# CloseLoopStepperMotor.net
KiCad netlist of a schematic drawn in Altium Designer
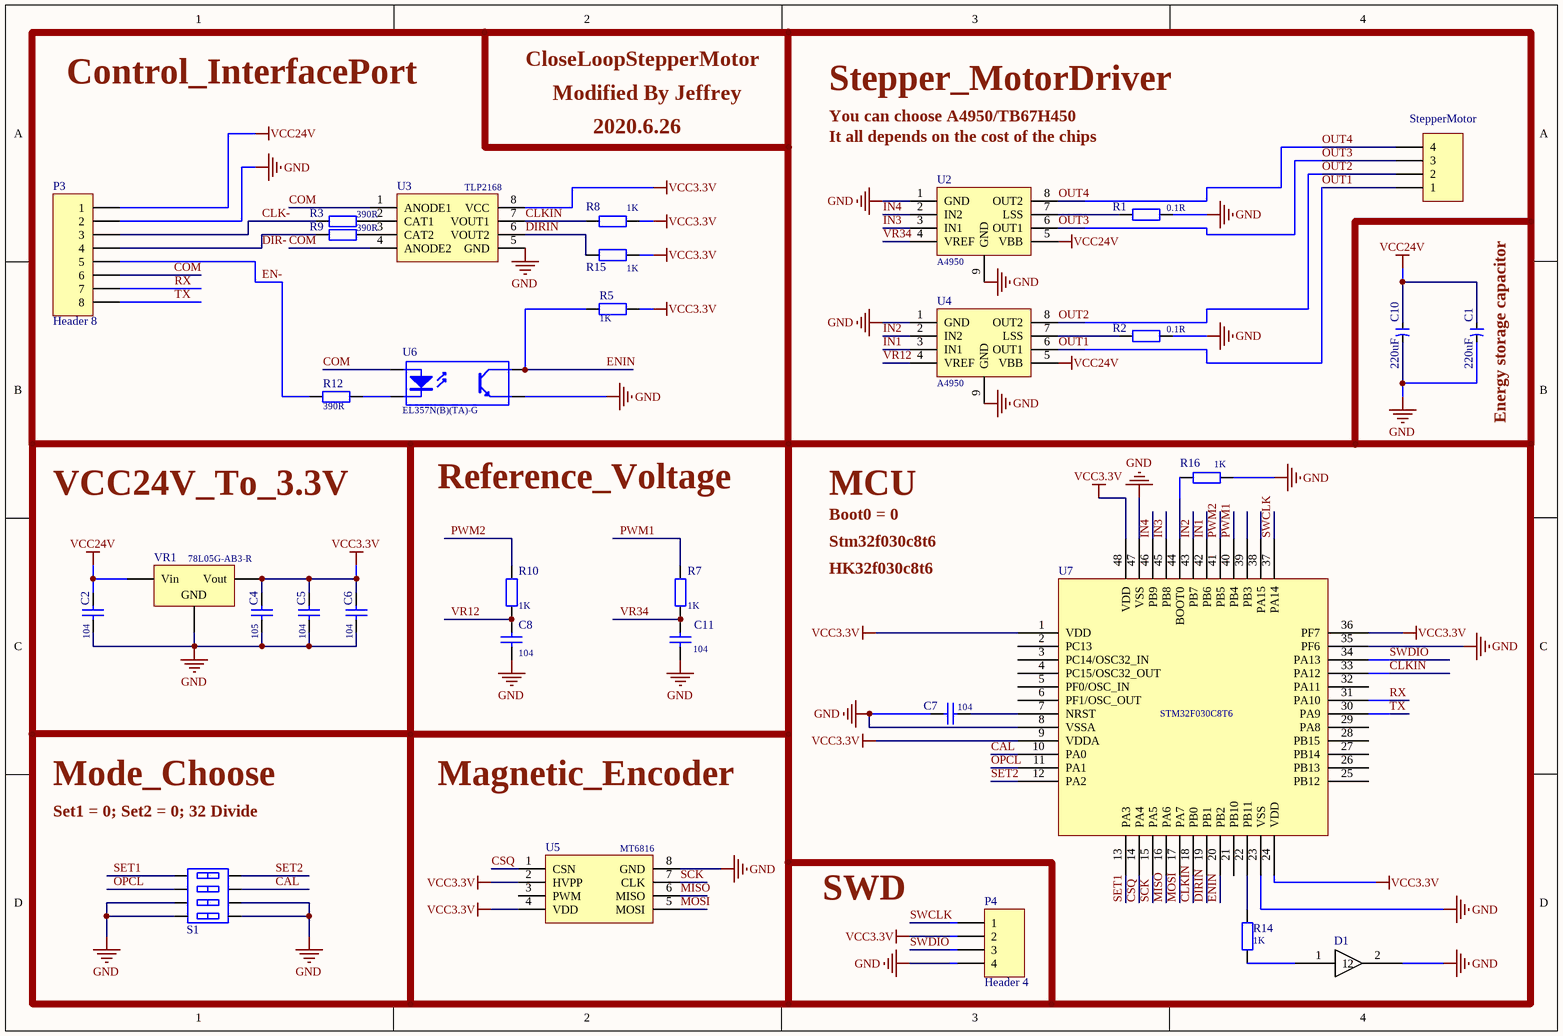
[diagram p0: CloseLoopStepperMotor.SchDoc]

(export (version "E")
  (design (tool "Eeschema 10.0.6"))
  (components
    (comp (ref "C1")
      (value "220uF")
      (footprint "CAP 2.5*6.3*11.2 - GD")
      (description "Polarized Capacitor (Axial)")
      (fields (field (name "Comment") "CAP POL") (field (name "PUBLISHER") "Altium Limited"))
      (libsource (lib "MySchib") (part "CAP POL"))
    )
    (comp (ref "C2")
      (value "104")
      (footprint "C 0603_M")
      (description "贴片电容")
      (libsource (lib "Miscellaneous Devices LC") (part "0805 100nF(104) 10% 50V"))
    )
    (comp (ref "C4")
      (value "105")
      (footprint "C 0603_M")
      (description "贴片电容")
      (libsource (lib "Miscellaneous Devices LC") (part "0805 1uF (105) 10% 50V"))
    )
    (comp (ref "C5")
      (value "104")
      (footprint "C 0603_M")
      (description "贴片电容")
      (libsource (lib "Miscellaneous Devices LC") (part "0805 100nF(104) 10% 50V"))
    )
    (comp (ref "C6")
      (value "104")
      (footprint "C 0603_M")
      (description "贴片电容")
      (libsource (lib "Miscellaneous Devices LC") (part "0805 100nF(104) 10% 50V"))
    )
    (comp (ref "C7")
      (value "104")
      (footprint "C 0603_M")
      (description "贴片电容")
      (libsource (lib "Miscellaneous Devices LC") (part "0805 100nF(104) 10% 50V"))
    )
    (comp (ref "C8")
      (value "104")
      (footprint "C 0603_M")
      (description "贴片电容")
      (libsource (lib "Miscellaneous Devices LC") (part "0805 100nF(104) 10% 50V"))
    )
    (comp (ref "C10")
      (value "220uF")
      (footprint "CAP 2.5*6.3*11.2 - GD")
      (description "Polarized Capacitor (Axial)")
      (fields (field (name "Comment") "CAP POL") (field (name "PUBLISHER") "Altium Limited"))
      (libsource (lib "MySchib") (part "CAP POL"))
    )
    (comp (ref "C11")
      (value "104")
      (footprint "C 0603_M")
      (description "贴片电容")
      (libsource (lib "Miscellaneous Devices LC") (part "0805 100nF(104) 10% 50V"))
    )
    (comp (ref "D1")
      (value "~")
      (footprint "LED 0603B")
      (libsource (lib "CloseLoopStepperMotor") (part "Diode"))
    )
    (comp (ref "P3")
      (value "Header 8")
      (footprint "PH2.0-WS-8P")
      (description "Header, 8-Pin")
      (fields (field (name "PUBLISHER") "Altium Limited"))
      (libsource (lib "Miscellaneous Connectors") (part "Header 8"))
    )
    (comp (ref "P4")
      (value "Header 4")
      (footprint "HDR2.54-LI-4P")
      (description "Header, 4-Pin")
      (fields (field (name "PUBLISHER") "Altium Limited"))
      (libsource (lib "Miscellaneous Connectors") (part "Header 4"))
    )
    (comp (ref "R1")
      (value "0.1R")
      (footprint "1206_R")
      (description "贴片电阻")
      (libsource (lib "Miscellaneous Devices LC") (part "1206 0.1Ω (R100) 1%"))
    )
    (comp (ref "R2")
      (value "0.1R")
      (footprint "1206_R")
      (description "贴片电阻")
      (libsource (lib "Miscellaneous Devices LC") (part "1206 0.1Ω (R100) 1%"))
    )
    (comp (ref "R3")
      (value "390R")
      (footprint "R 0603_M")
      (description "贴片电阻")
      (libsource (lib "Miscellaneous Devices LC") (part "0805 390Ω (3900) 1%"))
    )
    (comp (ref "R5")
      (value "1K")
      (footprint "R 0603_M")
      (description "贴片电阻")
      (libsource (lib "") (part "0805 1KΩ (1001) 1%_2"))
    )
    (comp (ref "R7")
      (value "1K")
      (footprint "R 0603_M")
      (description "贴片电阻")
      (libsource (lib "Miscellaneous Devices LC") (part "0805 1KΩ (1001) 1%"))
    )
    (comp (ref "R8")
      (value "1K")
      (footprint "R 0603_M")
      (description "贴片电阻")
      (libsource (lib "") (part "0805 1KΩ (1001) 1%_2"))
    )
    (comp (ref "R9")
      (value "390R")
      (footprint "R 0603_M")
      (description "贴片电阻")
      (libsource (lib "Miscellaneous Devices LC") (part "0805 390Ω (3900) 1%"))
    )
    (comp (ref "R10")
      (value "1K")
      (footprint "R 0603_M")
      (description "贴片电阻")
      (libsource (lib "") (part "0805 1KΩ (1001) 1%_1"))
    )
    (comp (ref "R12")
      (value "390R")
      (footprint "R 0603_M")
      (description "贴片电阻")
      (libsource (lib "Miscellaneous Devices LC") (part "0805 390Ω (3900) 1%"))
    )
    (comp (ref "R14")
      (value "1K")
      (footprint "R 0603_M")
      (description "贴片电阻")
      (libsource (lib "") (part "0805 1KΩ (1001) 1%_1"))
    )
    (comp (ref "R15")
      (value "1K")
      (footprint "R 0603_M")
      (description "贴片电阻")
      (libsource (lib "") (part "0805 1KΩ (1001) 1%_3"))
    )
    (comp (ref "R16")
      (value "1K")
      (footprint "R 0603_M")
      (description "贴片电阻")
      (libsource (lib "") (part "0805 1KΩ (1001) 1%_2"))
    )
    (comp (ref "S1")
      (value "SWDIP-4")
      (footprint "CSW1.27 SMD-4P")
      (description "DIP Switch, 4Position, SPST")
      (fields (field (name "PUBLISHER") "Altium Limited"))
      (libsource (lib "MySchib") (part "SWDIP-4"))
    )
    (comp (ref "StepperMotor")
      (value "HEADER4")
      (footprint "XH2.54-LI-4P")
      (description "Header, 4-Pin")
      (fields (field (name "PUBLISHER") "Altium Limited"))
      (libsource (lib "MySchib") (part "HEADER4"))
    )
    (comp (ref "U2")
      (value "A4950")
      (footprint "SOP8_M")
      (description "Dual Full-Bridge  DMOS PWM Motor Driver")
      (libsource (lib "MySchib") (part "A4950"))
    )
    (comp (ref "U3")
      (value "TLP2168")
      (footprint "SOP8_M")
      (description "HIGH SPEED 10MBit/s LOGIC GATE  PHOTOCOUPLER")
      (libsource (lib "MySchib") (part "TLP2168"))
    )
    (comp (ref "U4")
      (value "A4950")
      (footprint "SOP8_M")
      (description "Dual Full-Bridge  DMOS PWM Motor Driver")
      (libsource (lib "MySchib") (part "A4950"))
    )
    (comp (ref "U5")
      (value "MT6816")
      (footprint "SOP8_M")
      (description "GMR-Based Angle Sensor")
      (libsource (lib "MySchib") (part "MT6816"))
    )
    (comp (ref "U6")
      (value "EL357N(B)(TA)-G")
      (footprint "SOP4_M")
      (description "贴片光耦")
      (libsource (lib "Miscellaneous Devices LC") (part "EL357N(B)(TA)-G_[C6649]"))
    )
    (comp (ref "U7")
      (value "STM32F030C8T6")
      (footprint "LQFP48 7X7_M")
      (description "ARM")
      (libsource (lib "Miscellaneous Devices LC") (part "STM32F030C8T6"))
    )
    (comp (ref "VR1")
      (value "78L05G-AB3-R")
      (footprint "SOT-89(SOT-89-3)")
      (description "低压差线性稳压(LDO)")
      (libsource (lib "Miscellaneous Devices LC") (part "SOT-89 78L05G-AB3-R"))
    )
  )
  (nets
    (net (code "1") (name "/CAL") (class "Default")
      (node (ref "S1") (pin "4") (pinfunction "B2_4") (pintype "passive"))
      (node (ref "U7") (pin "10") (pinfunction "PA0_10") (pintype "passive"))
    )
    (net (code "2") (name "/CLK-") (class "Default")
      (node (ref "P3") (pin "3") (pinfunction "3_3") (pintype "passive"))
      (node (ref "R3") (pin "1") (pinfunction "1_1") (pintype "passive"))
    )
    (net (code "3") (name "/CLKIN") (class "Default")
      (node (ref "R8") (pin "1") (pinfunction "1_1") (pintype "passive"))
      (node (ref "U3") (pin "7") (pinfunction "VOUT1_7") (pintype "passive"))
      (node (ref "U7") (pin "18") (pinfunction "PB0_18") (pintype "passive"))
      (node (ref "U7") (pin "33") (pinfunction "PA12_33") (pintype "passive"))
    )
    (net (code "4") (name "/COM") (class "Default")
      (node (ref "P3") (pin "6") (pinfunction "6_6") (pintype "passive"))
      (node (ref "U3") (pin "1") (pinfunction "ANODE1_1") (pintype "passive"))
      (node (ref "U3") (pin "4") (pinfunction "ANODE2_4") (pintype "passive"))
      (node (ref "U6") (pin "1") (pinfunction "A_1") (pintype "passive"))
    )
    (net (code "5") (name "/CSQ") (class "Default")
      (node (ref "U5") (pin "1") (pinfunction "CSN_1") (pintype "passive"))
      (node (ref "U7") (pin "14") (pinfunction "PA4_14") (pintype "passive"))
    )
    (net (code "6") (name "/DIR-") (class "Default")
      (node (ref "P3") (pin "4") (pinfunction "4_4") (pintype "passive"))
      (node (ref "R9") (pin "1") (pinfunction "1_1") (pintype "passive"))
    )
    (net (code "7") (name "/DIRIN") (class "Default")
      (node (ref "R15") (pin "2") (pinfunction "2_2") (pintype "passive"))
      (node (ref "U3") (pin "6") (pinfunction "VOUT2_6") (pintype "passive"))
      (node (ref "U7") (pin "19") (pinfunction "PB1_19") (pintype "passive"))
    )
    (net (code "8") (name "/EN-") (class "Default")
      (node (ref "P3") (pin "5") (pinfunction "5_5") (pintype "passive"))
      (node (ref "R12") (pin "1") (pinfunction "1_1") (pintype "passive"))
    )
    (net (code "9") (name "/ENIN") (class "Default")
      (node (ref "R5") (pin "1") (pinfunction "1_1") (pintype "passive"))
      (node (ref "U6") (pin "4") (pinfunction "C_4") (pintype "passive"))
      (node (ref "U7") (pin "20") (pinfunction "PB2_20") (pintype "passive"))
    )
    (net (code "10") (name "/IN1") (class "Default")
      (node (ref "U4") (pin "3") (pinfunction "IN1_3") (pintype "passive"))
      (node (ref "U7") (pin "42") (pinfunction "PB6_42") (pintype "passive"))
    )
    (net (code "11") (name "/IN2") (class "Default")
      (node (ref "U4") (pin "2") (pinfunction "IN2_2") (pintype "passive"))
      (node (ref "U7") (pin "43") (pinfunction "PB7_43") (pintype "passive"))
    )
    (net (code "12") (name "/IN3") (class "Default")
      (node (ref "U2") (pin "3") (pinfunction "IN1_3") (pintype "passive"))
      (node (ref "U7") (pin "45") (pinfunction "PB8_45") (pintype "passive"))
    )
    (net (code "13") (name "/IN4") (class "Default")
      (node (ref "U2") (pin "2") (pinfunction "IN2_2") (pintype "passive"))
      (node (ref "U7") (pin "46") (pinfunction "PB9_46") (pintype "passive"))
    )
    (net (code "14") (name "/MISO") (class "Default")
      (node (ref "U5") (pin "6") (pinfunction "MISO_6") (pintype "passive"))
      (node (ref "U7") (pin "16") (pinfunction "PA6_16") (pintype "passive"))
    )
    (net (code "15") (name "/MOSI") (class "Default")
      (node (ref "U5") (pin "5") (pinfunction "MOSI_5") (pintype "passive"))
      (node (ref "U7") (pin "17") (pinfunction "PA7_17") (pintype "passive"))
    )
    (net (code "16") (name "/OPCL") (class "Default")
      (node (ref "S1") (pin "3") (pinfunction "A2_3") (pintype "passive"))
      (node (ref "U7") (pin "11") (pinfunction "PA1_11") (pintype "passive"))
    )
    (net (code "17") (name "/OUT1") (class "Default")
      (node (ref "StepperMotor") (pin "1") (pinfunction "1_1") (pintype "passive"))
      (node (ref "U4") (pin "6") (pinfunction "OUT1_6") (pintype "passive"))
    )
    (net (code "18") (name "/OUT2") (class "Default")
      (node (ref "StepperMotor") (pin "2") (pinfunction "2_2") (pintype "passive"))
      (node (ref "U4") (pin "8") (pinfunction "OUT2_8") (pintype "passive"))
    )
    (net (code "19") (name "/OUT3") (class "Default")
      (node (ref "StepperMotor") (pin "3") (pinfunction "3_3") (pintype "passive"))
      (node (ref "U2") (pin "6") (pinfunction "OUT1_6") (pintype "passive"))
    )
    (net (code "20") (name "/OUT4") (class "Default")
      (node (ref "StepperMotor") (pin "4") (pinfunction "4_4") (pintype "passive"))
      (node (ref "U2") (pin "8") (pinfunction "OUT2_8") (pintype "passive"))
    )
    (net (code "21") (name "/PWM1") (class "Default")
      (node (ref "R7") (pin "2") (pinfunction "2_2") (pintype "passive"))
      (node (ref "U7") (pin "40") (pinfunction "PB4_40") (pintype "passive"))
    )
    (net (code "22") (name "/PWM2") (class "Default")
      (node (ref "R10") (pin "1") (pinfunction "1_1") (pintype "passive"))
      (node (ref "U7") (pin "41") (pinfunction "PB5_41") (pintype "passive"))
    )
    (net (code "23") (name "/RX") (class "Default")
      (node (ref "P3") (pin "7") (pinfunction "7_7") (pintype "passive"))
      (node (ref "U7") (pin "31") (pinfunction "PA10_31") (pintype "passive"))
    )
    (net (code "24") (name "/SCK") (class "Default")
      (node (ref "U5") (pin "7") (pinfunction "CLK_7") (pintype "passive"))
      (node (ref "U7") (pin "15") (pinfunction "PA5_15") (pintype "passive"))
    )
    (net (code "25") (name "/SET1") (class "Default")
      (node (ref "S1") (pin "1") (pinfunction "A1_1") (pintype "passive"))
      (node (ref "U7") (pin "13") (pinfunction "PA3_13") (pintype "passive"))
    )
    (net (code "26") (name "/SET2") (class "Default")
      (node (ref "S1") (pin "2") (pinfunction "B1_2") (pintype "passive"))
      (node (ref "U7") (pin "12") (pinfunction "PA2_12") (pintype "passive"))
    )
    (net (code "27") (name "/SWCLK") (class "Default")
      (node (ref "P4") (pin "1") (pinfunction "1_1") (pintype "passive"))
      (node (ref "U7") (pin "37") (pinfunction "PA14_37") (pintype "passive"))
    )
    (net (code "28") (name "/SWDIO") (class "Default")
      (node (ref "P4") (pin "3") (pinfunction "3_3") (pintype "passive"))
      (node (ref "U7") (pin "34") (pinfunction "PA13_34") (pintype "passive"))
    )
    (net (code "29") (name "/TX") (class "Default")
      (node (ref "P3") (pin "8") (pinfunction "8_8") (pintype "passive"))
      (node (ref "U7") (pin "30") (pinfunction "PA9_30") (pintype "passive"))
    )
    (net (code "30") (name "/VR12") (class "Default")
      (node (ref "C8") (pin "1") (pinfunction "1_1") (pintype "passive"))
      (node (ref "R10") (pin "2") (pinfunction "2_2") (pintype "passive"))
      (node (ref "U4") (pin "4") (pinfunction "VREF_4") (pintype "passive"))
    )
    (net (code "31") (name "/VR34") (class "Default")
      (node (ref "C11") (pin "1") (pinfunction "1_1") (pintype "passive"))
      (node (ref "R7") (pin "1") (pinfunction "1_1") (pintype "passive"))
      (node (ref "U2") (pin "4") (pinfunction "VREF_4") (pintype "passive"))
    )
    (net (code "32") (name "GND") (class "Default")
      (node (ref "C1") (pin "2") (pinfunction "2_2") (pintype "passive"))
      (node (ref "C10") (pin "2") (pinfunction "2_2") (pintype "passive"))
      (node (ref "C11") (pin "2") (pinfunction "2_2") (pintype "passive"))
      (node (ref "C2") (pin "2") (pinfunction "2_2") (pintype "passive"))
      (node (ref "C4") (pin "2") (pinfunction "2_2") (pintype "passive"))
      (node (ref "C5") (pin "2") (pinfunction "2_2") (pintype "passive"))
      (node (ref "C6") (pin "2") (pinfunction "2_2") (pintype "passive"))
      (node (ref "C7") (pin "1") (pinfunction "1_1") (pintype "passive"))
      (node (ref "C8") (pin "2") (pinfunction "2_2") (pintype "passive"))
      (node (ref "D1") (pin "2") (pinfunction "2_2") (pintype "passive"))
      (node (ref "P3") (pin "2") (pinfunction "2_2") (pintype "passive"))
      (node (ref "P4") (pin "4") (pinfunction "4_4") (pintype "passive"))
      (node (ref "R1") (pin "1") (pinfunction "1_1") (pintype "passive"))
      (node (ref "R16") (pin "2") (pinfunction "2_2") (pintype "passive"))
      (node (ref "R2") (pin "1") (pinfunction "1_1") (pintype "passive"))
      (node (ref "S1") (pin "5") (pinfunction "A3_5") (pintype "passive"))
      (node (ref "S1") (pin "6") (pinfunction "B3_6") (pintype "passive"))
      (node (ref "S1") (pin "7") (pinfunction "A4_7") (pintype "passive"))
      (node (ref "S1") (pin "8") (pinfunction "B4_8") (pintype "passive"))
      (node (ref "U2") (pin "1") (pinfunction "GND_1") (pintype "passive"))
      (node (ref "U2") (pin "9") (pinfunction "GND_9") (pintype "passive"))
      (node (ref "U3") (pin "5") (pinfunction "GND_5") (pintype "passive"))
      (node (ref "U4") (pin "1") (pinfunction "GND_1") (pintype "passive"))
      (node (ref "U4") (pin "9") (pinfunction "GND_9") (pintype "passive"))
      (node (ref "U5") (pin "8") (pinfunction "GND_8") (pintype "passive"))
      (node (ref "U6") (pin "3") (pinfunction "E_3") (pintype "passive"))
      (node (ref "U7") (pin "23") (pinfunction "VSS_23") (pintype "passive"))
      (node (ref "U7") (pin "35") (pinfunction "PF6_35") (pintype "passive"))
      (node (ref "U7") (pin "47") (pinfunction "VSS_47") (pintype "passive"))
      (node (ref "U7") (pin "8") (pinfunction "VSSA_8") (pintype "passive"))
      (node (ref "VR1") (pin "2") (pinfunction "GND_2") (pintype "passive"))
    )
    (net (code "33") (name "Net-(D1-Pad1)") (class "Default")
      (node (ref "D1") (pin "1") (pinfunction "1_1") (pintype "passive"))
      (node (ref "R14") (pin "2") (pinfunction "2_2") (pintype "passive"))
    )
    (net (code "34") (name "Net-(U2-LSS)") (class "Default")
      (node (ref "R1") (pin "2") (pinfunction "2_2") (pintype "passive"))
      (node (ref "U2") (pin "7") (pinfunction "LSS_7") (pintype "passive"))
    )
    (net (code "35") (name "Net-(U3-CAT1)") (class "Default")
      (node (ref "R3") (pin "2") (pinfunction "2_2") (pintype "passive"))
      (node (ref "U3") (pin "2") (pinfunction "CAT1_2") (pintype "passive"))
    )
    (net (code "36") (name "Net-(U3-CAT2)") (class "Default")
      (node (ref "R9") (pin "2") (pinfunction "2_2") (pintype "passive"))
      (node (ref "U3") (pin "3") (pinfunction "CAT2_3") (pintype "passive"))
    )
    (net (code "37") (name "Net-(U4-LSS)") (class "Default")
      (node (ref "R2") (pin "2") (pinfunction "2_2") (pintype "passive"))
      (node (ref "U4") (pin "7") (pinfunction "LSS_7") (pintype "passive"))
    )
    (net (code "38") (name "Net-(U6-K)") (class "Default")
      (node (ref "R12") (pin "2") (pinfunction "2_2") (pintype "passive"))
      (node (ref "U6") (pin "2") (pinfunction "K_2") (pintype "passive"))
    )
    (net (code "39") (name "Net-(U7-BOOT0)") (class "Default")
      (node (ref "R16") (pin "1") (pinfunction "1_1") (pintype "passive"))
      (node (ref "U7") (pin "44") (pinfunction "BOOT0_44") (pintype "passive"))
    )
    (net (code "40") (name "Net-(U7-NRST)") (class "Default")
      (node (ref "C7") (pin "2") (pinfunction "2_2") (pintype "passive"))
      (node (ref "U7") (pin "7") (pinfunction "NRST_7") (pintype "passive"))
    )
    (net (code "41") (name "Net-(U7-PB11)") (class "Default")
      (node (ref "R14") (pin "1") (pinfunction "1_1") (pintype "passive"))
      (node (ref "U7") (pin "22") (pinfunction "PB11_22") (pintype "passive"))
    )
    (net (code "42") (name "VCC3.3V") (class "Default")
      (node (ref "C4") (pin "1") (pinfunction "1_1") (pintype "passive"))
      (node (ref "C5") (pin "1") (pinfunction "1_1") (pintype "passive"))
      (node (ref "C6") (pin "1") (pinfunction "1_1") (pintype "passive"))
      (node (ref "P4") (pin "2") (pinfunction "2_2") (pintype "passive"))
      (node (ref "R15") (pin "1") (pinfunction "1_1") (pintype "passive"))
      (node (ref "R5") (pin "2") (pinfunction "2_2") (pintype "passive"))
      (node (ref "R8") (pin "2") (pinfunction "2_2") (pintype "passive"))
      (node (ref "U3") (pin "8") (pinfunction "VCC_8") (pintype "passive"))
      (node (ref "U5") (pin "2") (pinfunction "HVPP_2") (pintype "passive"))
      (node (ref "U5") (pin "4") (pinfunction "VDD_4") (pintype "passive"))
      (node (ref "U7") (pin "1") (pinfunction "VDD_1") (pintype "passive"))
      (node (ref "U7") (pin "24") (pinfunction "VDD_24") (pintype "passive"))
      (node (ref "U7") (pin "36") (pinfunction "PF7_36") (pintype "passive"))
      (node (ref "U7") (pin "48") (pinfunction "VDD_48") (pintype "passive"))
      (node (ref "U7") (pin "9") (pinfunction "VDDA_9") (pintype "passive"))
      (node (ref "VR1") (pin "1") (pinfunction "Vout_1") (pintype "passive"))
    )
    (net (code "43") (name "VCC24V") (class "Default")
      (node (ref "C1") (pin "1") (pinfunction "1_1") (pintype "passive"))
      (node (ref "C10") (pin "1") (pinfunction "1_1") (pintype "passive"))
      (node (ref "C2") (pin "1") (pinfunction "1_1") (pintype "passive"))
      (node (ref "P3") (pin "1") (pinfunction "1_1") (pintype "passive"))
      (node (ref "U2") (pin "5") (pinfunction "VBB_5") (pintype "passive"))
      (node (ref "U4") (pin "5") (pinfunction "VBB_5") (pintype "passive"))
      (node (ref "VR1") (pin "3") (pinfunction "Vin_3") (pintype "passive"))
    )
    (net (code "44") (name "unconnected-(U5-PWM-Pad3)") (class "Default")
      (node (ref "U5") (pin "3") (pinfunction "PWM_3") (pintype "passive"))
    )
    (net (code "45") (name "unconnected-(U7-PA8-Pad29)") (class "Default")
      (node (ref "U7") (pin "29") (pinfunction "PA8_29") (pintype "passive"))
    )
    (net (code "46") (name "unconnected-(U7-PA11-Pad32)") (class "Default")
      (node (ref "U7") (pin "32") (pinfunction "PA11_32") (pintype "passive"))
    )
    (net (code "47") (name "unconnected-(U7-PA15-Pad38)") (class "Default")
      (node (ref "U7") (pin "38") (pinfunction "PA15_38") (pintype "passive"))
    )
    (net (code "48") (name "unconnected-(U7-PB3-Pad39)") (class "Default")
      (node (ref "U7") (pin "39") (pinfunction "PB3_39") (pintype "passive"))
    )
    (net (code "49") (name "unconnected-(U7-PB10-Pad21)") (class "Default")
      (node (ref "U7") (pin "21") (pinfunction "PB10_21") (pintype "passive"))
    )
    (net (code "50") (name "unconnected-(U7-PB12-Pad25)") (class "Default")
      (node (ref "U7") (pin "25") (pinfunction "PB12_25") (pintype "passive"))
    )
    (net (code "51") (name "unconnected-(U7-PB13-Pad26)") (class "Default")
      (node (ref "U7") (pin "26") (pinfunction "PB13_26") (pintype "passive"))
    )
    (net (code "52") (name "unconnected-(U7-PB14-Pad27)") (class "Default")
      (node (ref "U7") (pin "27") (pinfunction "PB14_27") (pintype "passive"))
    )
    (net (code "53") (name "unconnected-(U7-PB15-Pad28)") (class "Default")
      (node (ref "U7") (pin "28") (pinfunction "PB15_28") (pintype "passive"))
    )
    (net (code "54") (name "unconnected-(U7-PC13-Pad2)") (class "Default")
      (node (ref "U7") (pin "2") (pinfunction "PC13_2") (pintype "passive"))
    )
    (net (code "55") (name "unconnected-(U7-PC14{slash}OSC32_IN-Pad3)") (class "Default")
      (node (ref "U7") (pin "3") (pinfunction "PC14/OSC32_IN_3") (pintype "passive"))
    )
    (net (code "56") (name "unconnected-(U7-PC15{slash}OSC32_OUT-Pad4)") (class "Default")
      (node (ref "U7") (pin "4") (pinfunction "PC15/OSC32_OUT_4") (pintype "passive"))
    )
    (net (code "57") (name "unconnected-(U7-PF0{slash}OSC_IN-Pad5)") (class "Default")
      (node (ref "U7") (pin "5") (pinfunction "PF0/OSC_IN_5") (pintype "passive"))
    )
    (net (code "58") (name "unconnected-(U7-PF1{slash}OSC_OUT-Pad6)") (class "Default")
      (node (ref "U7") (pin "6") (pinfunction "PF1/OSC_OUT_6") (pintype "passive"))
    )
  )
)
